# AD630.net
KiCad netlist of a schematic drawn in EasyEDA Pro
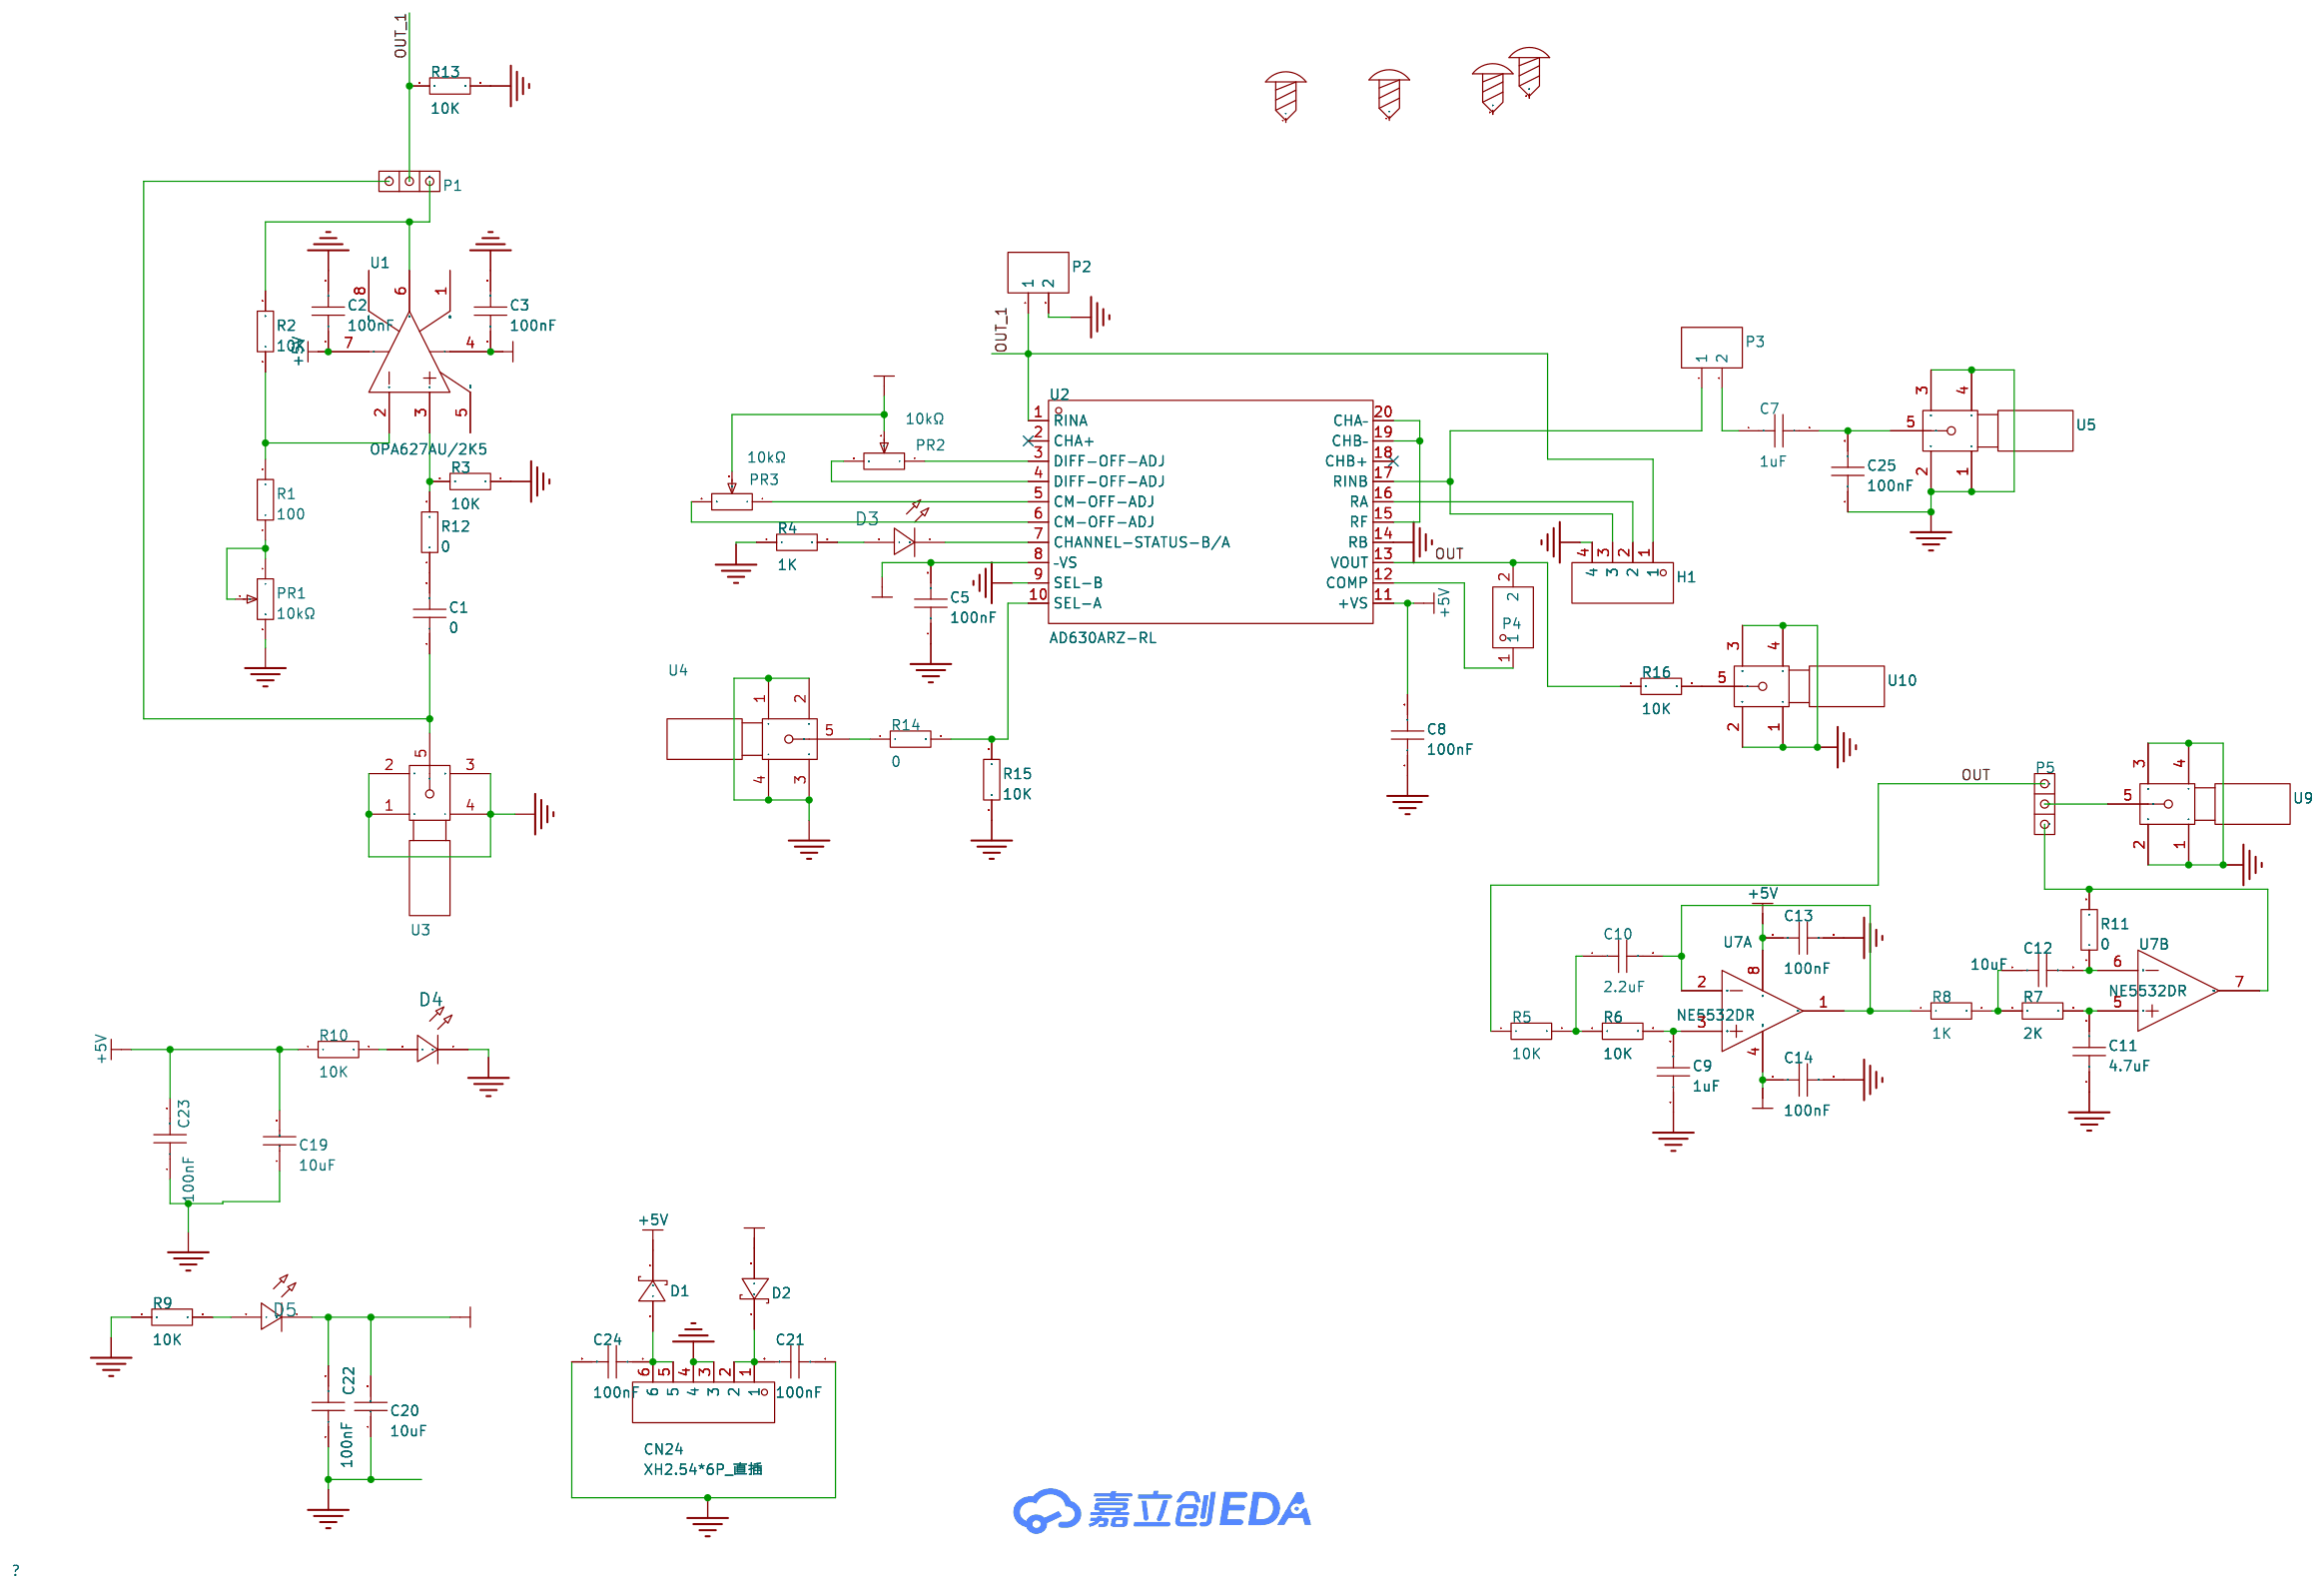
[diagram p0: schematic sheet]

(export (version "E")
  (design (tool "Eeschema 10.0.6"))
  (components
    (comp (ref "C1")
      (value "0")
      (footprint "easyedapro:C0603")
      (libsource (lib "easyedapro") (part "CapAcitance"))
    )
    (comp (ref "C2")
      (value "100nF")
      (footprint "easyedapro:C0603")
      (libsource (lib "easyedapro") (part "CapAcitance"))
    )
    (comp (ref "C3")
      (value "100nF")
      (footprint "easyedapro:C0603")
      (libsource (lib "easyedapro") (part "CapAcitance"))
    )
    (comp (ref "C5")
      (value "100nF")
      (footprint "easyedapro:C0603")
      (libsource (lib "easyedapro") (part "CapAcitance"))
    )
    (comp (ref "C7")
      (value "1uF")
      (footprint "easyedapro:C0603")
      (libsource (lib "easyedapro") (part "CapAcitance"))
    )
    (comp (ref "C8")
      (value "100nF")
      (footprint "easyedapro:C0603")
      (libsource (lib "easyedapro") (part "CapAcitance"))
    )
    (comp (ref "C9")
      (value "1uF")
      (footprint "easyedapro:C0603")
      (libsource (lib "easyedapro") (part "CapAcitance"))
    )
    (comp (ref "C10")
      (value "2.2uF")
      (footprint "easyedapro:C0603")
      (libsource (lib "easyedapro") (part "CapAcitance"))
    )
    (comp (ref "C11")
      (value "4.7uF")
      (footprint "easyedapro:C0603")
      (libsource (lib "easyedapro") (part "CapAcitance"))
    )
    (comp (ref "C12")
      (value "10uF")
      (footprint "easyedapro:C0603")
      (libsource (lib "easyedapro") (part "CapAcitance"))
    )
    (comp (ref "C13")
      (value "100nF")
      (footprint "easyedapro:C0603")
      (libsource (lib "easyedapro") (part "CapAcitance"))
    )
    (comp (ref "C14")
      (value "100nF")
      (footprint "easyedapro:C0603")
      (libsource (lib "easyedapro") (part "CapAcitance"))
    )
    (comp (ref "C19")
      (value "10uF")
      (footprint "easyedapro:C1210")
      (description "容值:10uF;精度:±10%;额定电压:25V;材质(温度系数):X7R;")
      (fields
        (field (name "Manufacturer Part") "CL32B106KAJNNNE")
        (field (name "Manufacturer") "SAMSUNG(三星)")
      )
      (libsource (lib "easyedapro") (part "CL32B106KAJNNNE"))
    )
    (comp (ref "C20")
      (value "10uF")
      (footprint "easyedapro:C1210")
      (description "容值:10uF;精度:±10%;额定电压:25V;材质(温度系数):X7R;")
      (fields
        (field (name "Manufacturer Part") "CL32B106KAJNNNE")
        (field (name "Manufacturer") "SAMSUNG(三星)")
      )
      (libsource (lib "easyedapro") (part "CL32B106KAJNNNE"))
    )
    (comp (ref "C21")
      (value "100nF")
      (footprint "easyedapro:C0603")
      (libsource (lib "easyedapro") (part "CapAcitance"))
    )
    (comp (ref "C22")
      (value "100nF")
      (footprint "easyedapro:C0603")
      (libsource (lib "easyedapro") (part "CapAcitance"))
    )
    (comp (ref "C23")
      (value "100nF")
      (footprint "easyedapro:C0603")
      (libsource (lib "easyedapro") (part "CapAcitance"))
    )
    (comp (ref "C24")
      (value "100nF")
      (footprint "easyedapro:C0603")
      (libsource (lib "easyedapro") (part "CapAcitance"))
    )
    (comp (ref "C25")
      (value "100nF")
      (footprint "easyedapro:C0603")
      (libsource (lib "easyedapro") (part "CapAcitance"))
    )
    (comp (ref "CN24")
      (value "XH2.54*6P_直插")
      (footprint "easyedapro:CONN-TH_XH2.54-6P")
      (libsource (lib "easyedapro") (part "XH2.54*6P_直插"))
    )
    (comp (ref "D1")
      (value "SD103AWS")
      (footprint "easyedapro:SOD-323_L1.8-W1.3-LS2.5-RD")
      (description "正向压降(Vf):600mV@200mA;直流反向耐压(Vr):40V;整流电流:350mA;")
      (fields (field (name "Manufacturer") "Hottech(合科泰)"))
      (libsource (lib "easyedapro") (part "SD103AWS_C181207"))
    )
    (comp (ref "D2")
      (value "SD103AWS")
      (footprint "easyedapro:SOD-323_L1.8-W1.3-LS2.5-RD")
      (description "正向压降(Vf):600mV@200mA;直流反向耐压(Vr):40V;整流电流:350mA;")
      (fields (field (name "Manufacturer") "Hottech(合科泰)"))
      (libsource (lib "easyedapro") (part "SD103AWS_C181207"))
    )
    (comp (ref "D3")
      (value "~")
      (footprint "easyedapro:LED_0805")
      (libsource (lib "easyedapro") (part "LED_R"))
    )
    (comp (ref "D4")
      (value "~")
      (footprint "easyedapro:LED_0805")
      (libsource (lib "easyedapro") (part "LED_R"))
    )
    (comp (ref "D5")
      (value "~")
      (footprint "easyedapro:LED_0805")
      (libsource (lib "easyedapro") (part "LED_R"))
    )
    (comp (ref "H1")
      (value "~")
      (footprint "easyedapro:HDR-TH_4P-P2.54-V-M")
      (libsource (lib "easyedapro") (part "PZ254V-11-04P"))
    )
    (comp (ref "P1") (value "~") (footprint "easyedapro:1*3跳线") (libsource (lib "easyedapro") (part "1*3跳线")))
    (comp (ref "P2")
      (value "~")
      (footprint "easyedapro:HDR-TH_2P-P2.54-V-F")
      (libsource (lib "easyedapro") (part "Header-Female-2.54_1x2"))
    )
    (comp (ref "P3")
      (value "~")
      (footprint "easyedapro:HDR-TH_2P-P2.54-V-F")
      (libsource (lib "easyedapro") (part "Header-Female-2.54_1x2"))
    )
    (comp (ref "P4")
      (value "~")
      (footprint "easyedapro:HDR-TH_2P-P2.54-V-M-2")
      (libsource (lib "easyedapro") (part "HDR-M-2.54_2x1"))
    )
    (comp (ref "P5") (value "~") (footprint "easyedapro:1*3跳线") (libsource (lib "easyedapro") (part "1*3跳线")))
    (comp (ref "PR1")
      (value "10kΩ")
      (footprint "easyedapro:R_3296")
      (libsource (lib "easyedapro") (part "R_3296"))
    )
    (comp (ref "PR2")
      (value "10kΩ")
      (footprint "easyedapro:R_3296")
      (libsource (lib "easyedapro") (part "R_3296"))
    )
    (comp (ref "PR3")
      (value "10kΩ")
      (footprint "easyedapro:R_3296")
      (libsource (lib "easyedapro") (part "R_3296"))
    )
    (comp (ref "R1") (value "100") (footprint "easyedapro:R0805") (libsource (lib "easyedapro") (part "电阻")))
    (comp (ref "R2") (value "10K") (footprint "easyedapro:R0805") (libsource (lib "easyedapro") (part "电阻")))
    (comp (ref "R3") (value "10K") (footprint "easyedapro:R0805") (libsource (lib "easyedapro") (part "电阻")))
    (comp (ref "R4") (value "1K") (footprint "easyedapro:R0805") (libsource (lib "easyedapro") (part "电阻")))
    (comp (ref "R5") (value "10K") (footprint "easyedapro:R0805") (libsource (lib "easyedapro") (part "电阻")))
    (comp (ref "R6") (value "10K") (footprint "easyedapro:R0805") (libsource (lib "easyedapro") (part "电阻")))
    (comp (ref "R7") (value "2K") (footprint "easyedapro:R0805") (libsource (lib "easyedapro") (part "电阻")))
    (comp (ref "R8") (value "1K") (footprint "easyedapro:R0805") (libsource (lib "easyedapro") (part "电阻")))
    (comp (ref "R9") (value "10K") (footprint "easyedapro:R0805") (libsource (lib "easyedapro") (part "电阻")))
    (comp (ref "R10") (value "10K") (footprint "easyedapro:R0805") (libsource (lib "easyedapro") (part "电阻")))
    (comp (ref "R11") (value "0") (footprint "easyedapro:R0805") (libsource (lib "easyedapro") (part "电阻")))
    (comp (ref "R12") (value "0") (footprint "easyedapro:R0805") (libsource (lib "easyedapro") (part "电阻")))
    (comp (ref "R13") (value "10K") (footprint "easyedapro:R0805") (libsource (lib "easyedapro") (part "电阻")))
    (comp (ref "R14") (value "0") (footprint "easyedapro:R0805") (libsource (lib "easyedapro") (part "电阻")))
    (comp (ref "R15") (value "10K") (footprint "easyedapro:R0805") (libsource (lib "easyedapro") (part "电阻")))
    (comp (ref "R16") (value "10K") (footprint "easyedapro:R0805") (libsource (lib "easyedapro") (part "电阻")))
    (comp (ref "SCREW1")
      (value "~")
      (footprint "easyedapro:M3螺丝")
      (libsource (lib "easyedapro") (part "螺丝孔"))
    )
    (comp (ref "SCREW2")
      (value "~")
      (footprint "easyedapro:M3螺丝")
      (libsource (lib "easyedapro") (part "螺丝孔"))
    )
    (comp (ref "SCREW3")
      (value "~")
      (footprint "easyedapro:M3螺丝")
      (libsource (lib "easyedapro") (part "螺丝孔"))
    )
    (comp (ref "SCREW4")
      (value "~")
      (footprint "easyedapro:M3螺丝")
      (libsource (lib "easyedapro") (part "螺丝孔"))
    )
    (comp (ref "U1")
      (value "OPA627AU/2K5")
      (footprint "easyedapro:SOIC-8_L5.0-W4.0-P1.27-LS6.0-BL")
      (description "放大器数:单路;增益带宽积(GBP):16MHz;输入偏置电流(Ib):2pA;压摆率(SR):55V/us;轨到轨:-;")
      (fields (field (name "Manufacturer") "TI(德州仪器)"))
      (libsource (lib "easyedapro") (part "OPA627AU"))
    )
    (comp (ref "U2")
      (value "AD630ARZ-RL")
      (footprint "easyedapro:SOIC-20_L12.8-W7.5-P1.27-LS10.3-BL")
      (description "频率范围:-;增益:110dB;输出功率:-;本底噪声:-;噪声系数:-;")
      (fields (field (name "Manufacturer") "ADI(亚德诺)"))
      (libsource (lib "easyedapro") (part "AD630ARZ-RL"))
    )
    (comp (ref "U3") (value "~") (footprint "easyedapro:SMA") (libsource (lib "easyedapro") (part "SMA")))
    (comp (ref "U4") (value "~") (footprint "easyedapro:SMA") (libsource (lib "easyedapro") (part "SMA")))
    (comp (ref "U5") (value "~") (footprint "easyedapro:SMA") (libsource (lib "easyedapro") (part "SMA")))
    (comp (ref "U7")
      (value "NE5532DR")
      (footprint "easyedapro:SOIC-8_L4.9-W3.9-P1.27-LS6.0-BL")
      (description "放大器数:双路;增益带宽积(GBP):10MHz;输入偏置电流(Ib):200nA;压摆率(SR):9V/us;带宽(-3db):-;")
      (fields (field (name "Manufacturer") "TI(德州仪器)"))
      (libsource (lib "easyedapro") (part "NE5532DR"))
    )
    (comp (ref "U9") (value "~") (footprint "easyedapro:SMA") (libsource (lib "easyedapro") (part "SMA")))
    (comp (ref "U10") (value "~") (footprint "easyedapro:SMA") (libsource (lib "easyedapro") (part "SMA")))
  )
  (nets
    (net (code "1") (name "+5V") (class "Default")
      (node (ref "C13") (pin "1") (pinfunction "1_1") (pintype "input"))
      (node (ref "C19") (pin "2") (pinfunction "2_2") (pintype "input"))
      (node (ref "C2") (pin "1") (pinfunction "1_1") (pintype "input"))
      (node (ref "C23") (pin "2") (pinfunction "2_2") (pintype "input"))
      (node (ref "C8") (pin "2") (pinfunction "2_2") (pintype "input"))
      (node (ref "D1") (pin "1") (pinfunction "C_1") (pintype "unspecified"))
      (node (ref "R10") (pin "1") (pinfunction "1_1") (pintype "input"))
      (node (ref "U1") (pin "7") (pinfunction "V+_7") (pintype "unspecified"))
      (node (ref "U2") (pin "11") (pinfunction "+VS_11") (pintype "unspecified"))
      (node (ref "U7") (pin "8") (pinfunction "VCC+_8") (pintype "unspecified"))
    )
    (net (code "2") (name "-5V") (class "Default")
      (node (ref "C14") (pin "1") (pinfunction "1_1") (pintype "input"))
      (node (ref "C20") (pin "2") (pinfunction "2_2") (pintype "input"))
      (node (ref "C22") (pin "2") (pinfunction "2_2") (pintype "input"))
      (node (ref "C3") (pin "1") (pinfunction "1_1") (pintype "input"))
      (node (ref "C5") (pin "2") (pinfunction "2_2") (pintype "input"))
      (node (ref "D2") (pin "2") (pinfunction "A_2") (pintype "unspecified"))
      (node (ref "D5") (pin "1") (pinfunction "C_1") (pintype "input"))
      (node (ref "PR2") (pin "2") (pinfunction "2_2") (pintype "input"))
      (node (ref "PR3") (pin "2") (pinfunction "2_2") (pintype "input"))
      (node (ref "U1") (pin "4") (pinfunction "V-_4") (pintype "unspecified"))
      (node (ref "U2") (pin "8") (pinfunction "–VS_8") (pintype "unspecified"))
      (node (ref "U7") (pin "4") (pinfunction "VCC-/GND_4") (pintype "unspecified"))
    )
    (net (code "3") (name "/OUT") (class "Default")
      (node (ref "P4") (pin "2") (pinfunction "2_2") (pintype "input"))
      (node (ref "P5") (pin "1") (pinfunction "1_1") (pintype "input"))
      (node (ref "R16") (pin "1") (pinfunction "1_1") (pintype "input"))
      (node (ref "R5") (pin "1") (pinfunction "1_1") (pintype "input"))
      (node (ref "U2") (pin "13") (pinfunction "VOUT_13") (pintype "unspecified"))
    )
    (net (code "4") (name "/OUT_1") (class "Default")
      (node (ref "H1") (pin "1") (pinfunction "1_1") (pintype "unspecified"))
      (node (ref "P1") (pin "2") (pinfunction "2_2") (pintype "input"))
      (node (ref "P2") (pin "1") (pinfunction "1_1") (pintype "input"))
      (node (ref "R13") (pin "1") (pinfunction "1_1") (pintype "input"))
      (node (ref "U2") (pin "1") (pinfunction "RINA_1") (pintype "unspecified"))
    )
    (net (code "5") (name "GND") (class "Default")
      (node (ref "C11") (pin "1") (pinfunction "1_1") (pintype "input"))
      (node (ref "C13") (pin "2") (pinfunction "2_2") (pintype "input"))
      (node (ref "C14") (pin "2") (pinfunction "2_2") (pintype "input"))
      (node (ref "C19") (pin "1") (pinfunction "1_1") (pintype "input"))
      (node (ref "C2") (pin "2") (pinfunction "2_2") (pintype "input"))
      (node (ref "C20") (pin "1") (pinfunction "1_1") (pintype "input"))
      (node (ref "C21") (pin "1") (pinfunction "1_1") (pintype "input"))
      (node (ref "C22") (pin "1") (pinfunction "1_1") (pintype "input"))
      (node (ref "C23") (pin "1") (pinfunction "1_1") (pintype "input"))
      (node (ref "C24") (pin "2") (pinfunction "2_2") (pintype "input"))
      (node (ref "C25") (pin "1") (pinfunction "1_1") (pintype "input"))
      (node (ref "C3") (pin "2") (pinfunction "2_2") (pintype "input"))
      (node (ref "C5") (pin "1") (pinfunction "1_1") (pintype "input"))
      (node (ref "C8") (pin "1") (pinfunction "1_1") (pintype "input"))
      (node (ref "C9") (pin "1") (pinfunction "1_1") (pintype "input"))
      (node (ref "CN24") (pin "3") (pinfunction "3_3") (pintype "input"))
      (node (ref "CN24") (pin "4") (pinfunction "4_4") (pintype "input"))
      (node (ref "D4") (pin "1") (pinfunction "C_1") (pintype "input"))
      (node (ref "H1") (pin "4") (pinfunction "4_4") (pintype "unspecified"))
      (node (ref "P2") (pin "2") (pinfunction "2_2") (pintype "input"))
      (node (ref "PR1") (pin "3") (pinfunction "3_3") (pintype "input"))
      (node (ref "R13") (pin "2") (pinfunction "2_2") (pintype "input"))
      (node (ref "R15") (pin "1") (pinfunction "1_1") (pintype "input"))
      (node (ref "R3") (pin "1") (pinfunction "1_1") (pintype "input"))
      (node (ref "R4") (pin "1") (pinfunction "1_1") (pintype "input"))
      (node (ref "R9") (pin "1") (pinfunction "1_1") (pintype "input"))
      (node (ref "U10") (pin "1") (pinfunction "1_1") (pintype "input"))
      (node (ref "U10") (pin "2") (pinfunction "2_2") (pintype "input"))
      (node (ref "U10") (pin "3") (pinfunction "3_3") (pintype "input"))
      (node (ref "U10") (pin "4") (pinfunction "4_4") (pintype "input"))
      (node (ref "U2") (pin "14") (pinfunction "RB_14") (pintype "unspecified"))
      (node (ref "U2") (pin "9") (pinfunction "SEL-B_9") (pintype "unspecified"))
      (node (ref "U3") (pin "1") (pinfunction "1_1") (pintype "input"))
      (node (ref "U3") (pin "2") (pinfunction "2_2") (pintype "input"))
      (node (ref "U3") (pin "3") (pinfunction "3_3") (pintype "input"))
      (node (ref "U3") (pin "4") (pinfunction "4_4") (pintype "input"))
      (node (ref "U4") (pin "1") (pinfunction "1_1") (pintype "input"))
      (node (ref "U4") (pin "2") (pinfunction "2_2") (pintype "input"))
      (node (ref "U4") (pin "3") (pinfunction "3_3") (pintype "input"))
      (node (ref "U4") (pin "4") (pinfunction "4_4") (pintype "input"))
      (node (ref "U5") (pin "1") (pinfunction "1_1") (pintype "input"))
      (node (ref "U5") (pin "2") (pinfunction "2_2") (pintype "input"))
      (node (ref "U5") (pin "3") (pinfunction "3_3") (pintype "input"))
      (node (ref "U5") (pin "4") (pinfunction "4_4") (pintype "input"))
      (node (ref "U9") (pin "1") (pinfunction "1_1") (pintype "input"))
      (node (ref "U9") (pin "2") (pinfunction "2_2") (pintype "input"))
      (node (ref "U9") (pin "3") (pinfunction "3_3") (pintype "input"))
      (node (ref "U9") (pin "4") (pinfunction "4_4") (pintype "input"))
    )
    (net (code "6") (name "Net-(C1-Pad1)") (class "Default")
      (node (ref "C1") (pin "1") (pinfunction "1_1") (pintype "input"))
      (node (ref "P1") (pin "1") (pinfunction "1_1") (pintype "input"))
      (node (ref "U3") (pin "5") (pinfunction "5_5") (pintype "input"))
    )
    (net (code "7") (name "Net-(C1-Pad2)") (class "Default")
      (node (ref "C1") (pin "2") (pinfunction "2_2") (pintype "input"))
      (node (ref "R12") (pin "1") (pinfunction "1_1") (pintype "input"))
    )
    (net (code "8") (name "Net-(C7-Pad1)") (class "Default")
      (node (ref "C7") (pin "1") (pinfunction "1_1") (pintype "input"))
      (node (ref "P3") (pin "2") (pinfunction "2_2") (pintype "input"))
    )
    (net (code "9") (name "Net-(C10-Pad1)") (class "Default")
      (node (ref "C10") (pin "1") (pinfunction "1_1") (pintype "input"))
      (node (ref "R5") (pin "2") (pinfunction "2_2") (pintype "input"))
      (node (ref "R6") (pin "1") (pinfunction "1_1") (pintype "input"))
    )
    (net (code "10") (name "Net-(C12-Pad1)") (class "Default")
      (node (ref "C12") (pin "1") (pinfunction "1_1") (pintype "input"))
      (node (ref "R7") (pin "1") (pinfunction "1_1") (pintype "input"))
      (node (ref "R8") (pin "2") (pinfunction "2_2") (pintype "input"))
    )
    (net (code "11") (name "Net-(C25-Pad2)") (class "Default")
      (node (ref "C25") (pin "2") (pinfunction "2_2") (pintype "input"))
      (node (ref "C7") (pin "2") (pinfunction "2_2") (pintype "input"))
      (node (ref "U5") (pin "5") (pinfunction "5_5") (pintype "input"))
    )
    (net (code "12") (name "Net-(D1-A)") (class "Default")
      (node (ref "C24") (pin "1") (pinfunction "1_1") (pintype "input"))
      (node (ref "CN24") (pin "5") (pinfunction "5_5") (pintype "input"))
      (node (ref "CN24") (pin "6") (pinfunction "6_6") (pintype "input"))
      (node (ref "D1") (pin "2") (pinfunction "A_2") (pintype "unspecified"))
    )
    (net (code "13") (name "Net-(D2-C)") (class "Default")
      (node (ref "C21") (pin "2") (pinfunction "2_2") (pintype "input"))
      (node (ref "CN24") (pin "1") (pinfunction "1_1") (pintype "input"))
      (node (ref "CN24") (pin "2") (pinfunction "2_2") (pintype "input"))
      (node (ref "D2") (pin "1") (pinfunction "C_1") (pintype "unspecified"))
    )
    (net (code "14") (name "Net-(D3-A)") (class "Default")
      (node (ref "D3") (pin "2") (pinfunction "A_2") (pintype "input"))
      (node (ref "R4") (pin "2") (pinfunction "2_2") (pintype "input"))
    )
    (net (code "15") (name "Net-(D3-C)") (class "Default")
      (node (ref "D3") (pin "1") (pinfunction "C_1") (pintype "input"))
      (node (ref "U2") (pin "7") (pinfunction "CHANNEL-STATUS-B/A_7") (pintype "unspecified"))
    )
    (net (code "16") (name "Net-(D4-A)") (class "Default")
      (node (ref "D4") (pin "2") (pinfunction "A_2") (pintype "input"))
      (node (ref "R10") (pin "2") (pinfunction "2_2") (pintype "input"))
    )
    (net (code "17") (name "Net-(D5-A)") (class "Default")
      (node (ref "D5") (pin "2") (pinfunction "A_2") (pintype "input"))
      (node (ref "R9") (pin "2") (pinfunction "2_2") (pintype "input"))
    )
    (net (code "18") (name "Net-(P5-Pad2)") (class "Default")
      (node (ref "P5") (pin "2") (pinfunction "2_2") (pintype "input"))
      (node (ref "U9") (pin "5") (pinfunction "5_5") (pintype "input"))
    )
    (net (code "19") (name "Net-(PR1-Pad1)") (class "Default")
      (node (ref "PR1") (pin "1") (pinfunction "1_1") (pintype "input"))
      (node (ref "PR1") (pin "2") (pinfunction "2_2") (pintype "input"))
      (node (ref "R1") (pin "1") (pinfunction "1_1") (pintype "input"))
    )
    (net (code "20") (name "Net-(PR2-Pad1)") (class "Default")
      (node (ref "PR2") (pin "1") (pinfunction "1_1") (pintype "input"))
      (node (ref "U2") (pin "3") (pinfunction "DIFF-OFF-ADJ_3") (pintype "unspecified"))
    )
    (net (code "21") (name "Net-(PR2-Pad3)") (class "Default")
      (node (ref "PR2") (pin "3") (pinfunction "3_3") (pintype "input"))
      (node (ref "U2") (pin "4") (pinfunction "DIFF-OFF-ADJ_4") (pintype "unspecified"))
    )
    (net (code "22") (name "Net-(PR3-Pad1)") (class "Default")
      (node (ref "PR3") (pin "1") (pinfunction "1_1") (pintype "input"))
      (node (ref "U2") (pin "5") (pinfunction "CM-OFF-ADJ_5") (pintype "unspecified"))
    )
    (net (code "23") (name "Net-(PR3-Pad3)") (class "Default")
      (node (ref "PR3") (pin "3") (pinfunction "3_3") (pintype "input"))
      (node (ref "U2") (pin "6") (pinfunction "CM-OFF-ADJ_6") (pintype "unspecified"))
    )
    (net (code "24") (name "Net-(R14-Pad1)") (class "Default")
      (node (ref "R14") (pin "1") (pinfunction "1_1") (pintype "input"))
      (node (ref "U4") (pin "5") (pinfunction "5_5") (pintype "input"))
    )
    (net (code "25") (name "Net-(R16-Pad2)") (class "Default")
      (node (ref "R16") (pin "2") (pinfunction "2_2") (pintype "input"))
      (node (ref "U10") (pin "5") (pinfunction "5_5") (pintype "input"))
    )
    (net (code "26") (name "Net-(U1-IN+)") (class "Default")
      (node (ref "R12") (pin "2") (pinfunction "2_2") (pintype "input"))
      (node (ref "R3") (pin "2") (pinfunction "2_2") (pintype "input"))
      (node (ref "U1") (pin "3") (pinfunction "IN+_3") (pintype "unspecified"))
    )
    (net (code "27") (name "Net-(U1-IN-)") (class "Default")
      (node (ref "R1") (pin "2") (pinfunction "2_2") (pintype "input"))
      (node (ref "R2") (pin "1") (pinfunction "1_1") (pintype "input"))
      (node (ref "U1") (pin "2") (pinfunction "IN-_2") (pintype "unspecified"))
    )
    (net (code "28") (name "Net-(U1-OUT)") (class "Default")
      (node (ref "P1") (pin "3") (pinfunction "3_3") (pintype "input"))
      (node (ref "R2") (pin "2") (pinfunction "2_2") (pintype "input"))
      (node (ref "U1") (pin "6") (pinfunction "OUT_6") (pintype "output"))
    )
    (net (code "29") (name "Net-(U2-CHA–)") (class "Default")
      (node (ref "U2") (pin "15") (pinfunction "RF_15") (pintype "unspecified"))
      (node (ref "U2") (pin "19") (pinfunction "CHB–_19") (pintype "unspecified"))
      (node (ref "U2") (pin "20") (pinfunction "CHA–_20") (pintype "unspecified"))
    )
    (net (code "30") (name "Net-(U2-COMP)") (class "Default")
      (node (ref "P4") (pin "1") (pinfunction "1_1") (pintype "input"))
      (node (ref "U2") (pin "12") (pinfunction "COMP_12") (pintype "unspecified"))
    )
    (net (code "31") (name "Net-(U2-RA)") (class "Default")
      (node (ref "H1") (pin "2") (pinfunction "2_2") (pintype "unspecified"))
      (node (ref "U2") (pin "16") (pinfunction "RA_16") (pintype "unspecified"))
    )
    (net (code "32") (name "Net-(U2-RINB)") (class "Default")
      (node (ref "H1") (pin "3") (pinfunction "3_3") (pintype "unspecified"))
      (node (ref "P3") (pin "1") (pinfunction "1_1") (pintype "input"))
      (node (ref "U2") (pin "17") (pinfunction "RINB_17") (pintype "unspecified"))
    )
    (net (code "33") (name "Net-(U2-SEL-A)") (class "Default")
      (node (ref "R14") (pin "2") (pinfunction "2_2") (pintype "input"))
      (node (ref "R15") (pin "2") (pinfunction "2_2") (pintype "input"))
      (node (ref "U2") (pin "10") (pinfunction "SEL-A_10") (pintype "unspecified"))
    )
    (net (code "34") (name "Net-(U7A-IN1+)") (class "Default")
      (node (ref "C9") (pin "2") (pinfunction "2_2") (pintype "input"))
      (node (ref "R6") (pin "2") (pinfunction "2_2") (pintype "input"))
      (node (ref "U7") (pin "3") (pinfunction "IN1+_3") (pintype "unspecified"))
    )
    (net (code "35") (name "Net-(U7A-IN1-)") (class "Default")
      (node (ref "C10") (pin "2") (pinfunction "2_2") (pintype "input"))
      (node (ref "R8") (pin "1") (pinfunction "1_1") (pintype "input"))
      (node (ref "U7") (pin "1") (pinfunction "OUT1_1") (pintype "output"))
      (node (ref "U7") (pin "2") (pinfunction "IN1-_2") (pintype "unspecified"))
    )
    (net (code "36") (name "Net-(U7B-IN2+)") (class "Default")
      (node (ref "C11") (pin "2") (pinfunction "2_2") (pintype "input"))
      (node (ref "R7") (pin "2") (pinfunction "2_2") (pintype "input"))
      (node (ref "U7") (pin "5") (pinfunction "IN2+_5") (pintype "unspecified"))
    )
    (net (code "37") (name "Net-(U7B-IN2-)") (class "Default")
      (node (ref "C12") (pin "2") (pinfunction "2_2") (pintype "input"))
      (node (ref "R11") (pin "1") (pinfunction "1_1") (pintype "input"))
      (node (ref "U7") (pin "6") (pinfunction "IN2-_6") (pintype "unspecified"))
    )
    (net (code "38") (name "Net-(U7B-OUT2)") (class "Default")
      (node (ref "P5") (pin "3") (pinfunction "3_3") (pintype "input"))
      (node (ref "R11") (pin "2") (pinfunction "2_2") (pintype "input"))
      (node (ref "U7") (pin "7") (pinfunction "OUT2_7") (pintype "output"))
    )
    (net (code "39") (name "unconnected-(SCREW1-Pad1)") (class "Default")
      (node (ref "SCREW1") (pin "1") (pinfunction "1_1") (pintype "input"))
    )
    (net (code "40") (name "unconnected-(SCREW2-Pad1)") (class "Default")
      (node (ref "SCREW2") (pin "1") (pinfunction "1_1") (pintype "input"))
    )
    (net (code "41") (name "unconnected-(SCREW3-Pad1)") (class "Default")
      (node (ref "SCREW3") (pin "1") (pinfunction "1_1") (pintype "input"))
    )
    (net (code "42") (name "unconnected-(SCREW4-Pad1)") (class "Default")
      (node (ref "SCREW4") (pin "1") (pinfunction "1_1") (pintype "input"))
    )
    (net (code "43") (name "unconnected-(U1-No_Internal_Connection-Pad8)") (class "Default")
      (node (ref "U1") (pin "8") (pinfunction "No_Internal_Connection_8") (pintype "unspecified"))
    )
    (net (code "44") (name "unconnected-(U1-Offset_Trim-Pad1)") (class "Default")
      (node (ref "U1") (pin "1") (pinfunction "Offset_Trim_1") (pintype "unspecified"))
    )
    (net (code "45") (name "unconnected-(U1-Offset_Trim-Pad5)") (class "Default")
      (node (ref "U1") (pin "5") (pinfunction "Offset_Trim_5") (pintype "unspecified"))
    )
    (net (code "46") (name "unconnected-(U2-CHA+-Pad2)") (class "Default")
      (node (ref "U2") (pin "2") (pinfunction "CHA+_2") (pintype "unspecified+no_connect"))
    )
    (net (code "47") (name "unconnected-(U2-CHB+-Pad18)") (class "Default")
      (node (ref "U2") (pin "18") (pinfunction "CHB+_18") (pintype "unspecified+no_connect"))
    )
  )
)
